# TSAL_Proto18_rev3.net
KiCad netlist of a schematic drawn in EAGLE
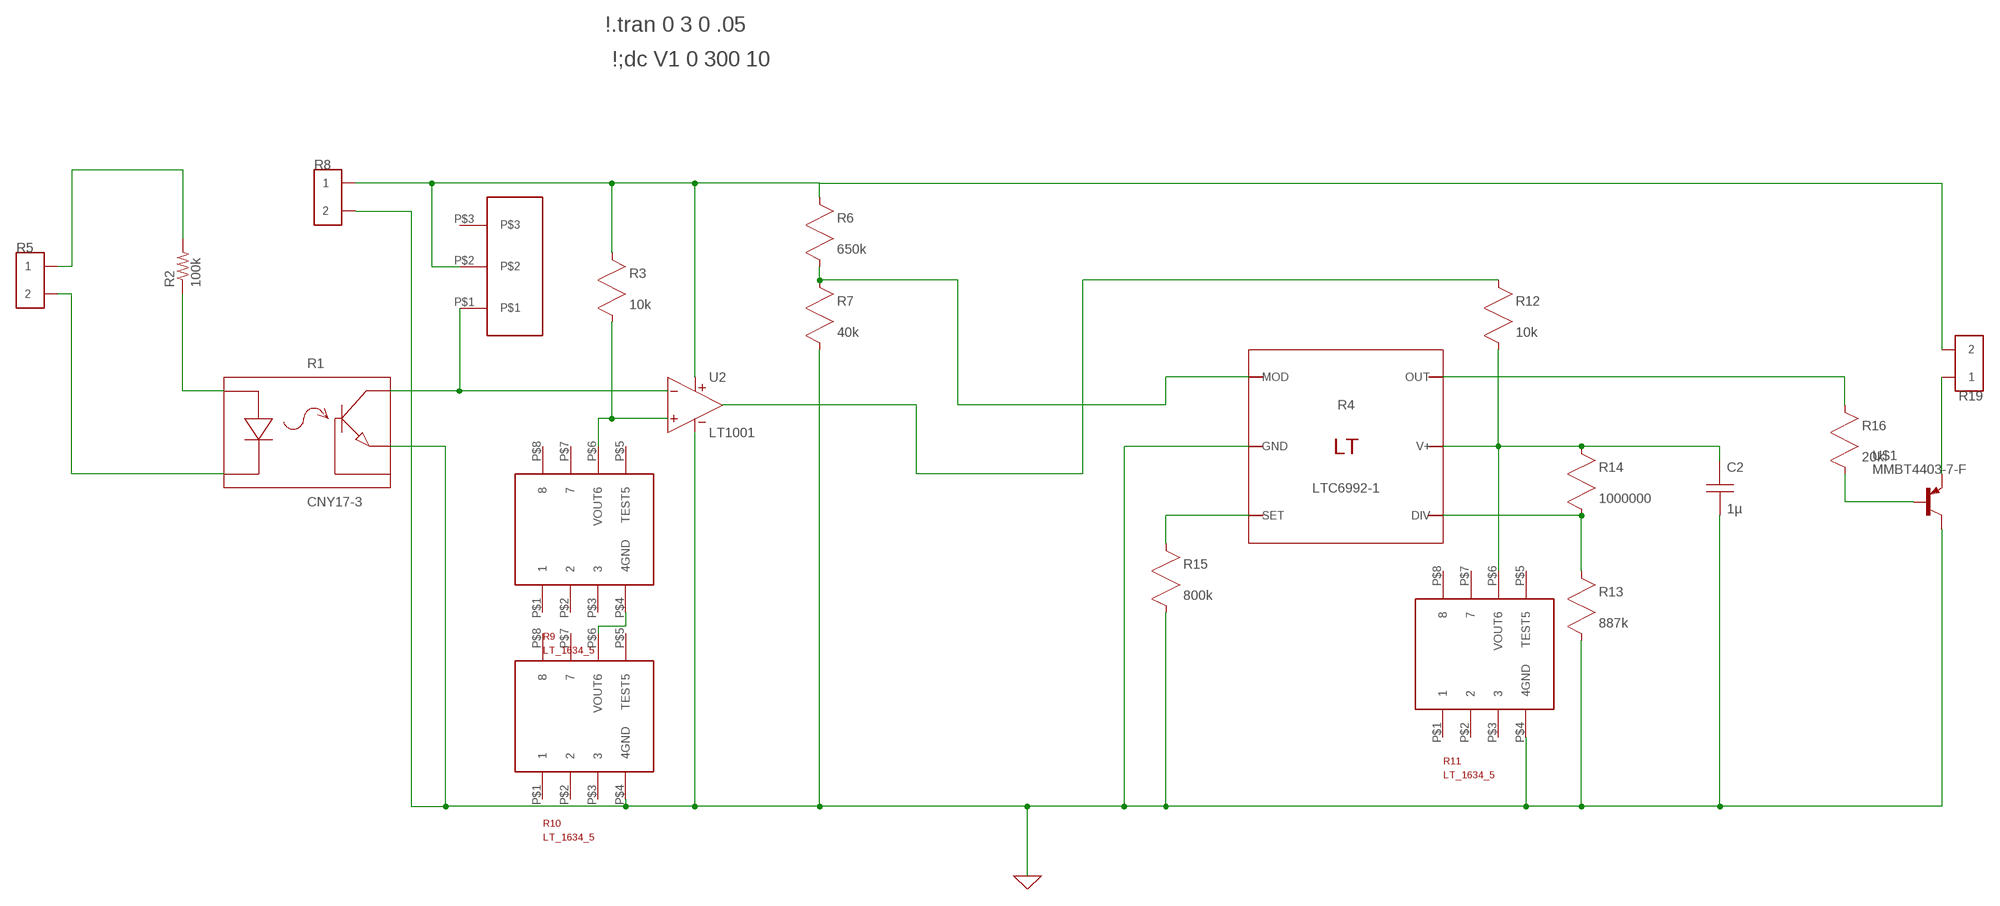
[diagram p0: schematic, sheet 1]

(export (version "E")
  (design (tool "Eeschema 10.0.6"))
  (components
    (comp (ref "C2")
      (value "1µ")
      (footprint "eagle-import:C0805")
      (libsource (lib "eagle-import") (part "CAP"))
    )
    (comp (ref "R1")
      (value "CNY17-3")
      (footprint "eagle-import:CNY17-3")
      (libsource (lib "eagle-import") (part "CNY17-3"))
    )
    (comp (ref "R2")
      (value "100k")
      (footprint "eagle-import:P0817_22")
      (libsource (lib "eagle-import") (part "R-US_0817/22"))
    )
    (comp (ref "R3")
      (value "10k")
      (footprint "eagle-import:R0805")
      (libsource (lib "eagle-import") (part "RES"))
    )
    (comp (ref "R4")
      (value "LTC6992-1")
      (footprint "eagle-import:LTC6992-1")
      (libsource (lib "eagle-import") (part "LTC6992-1"))
    )
    (comp (ref "R5")
      (value "CONN_2")
      (footprint "eagle-import:CONNECTOR_2")
      (libsource (lib "eagle-import") (part "CONN_2"))
    )
    (comp (ref "R6")
      (value "650k")
      (footprint "eagle-import:R0805")
      (libsource (lib "eagle-import") (part "RES"))
    )
    (comp (ref "R7")
      (value "40k")
      (footprint "eagle-import:R0805")
      (libsource (lib "eagle-import") (part "RES"))
    )
    (comp (ref "R8")
      (value "CONN_2")
      (footprint "eagle-import:CONNECTOR_2")
      (libsource (lib "eagle-import") (part "CONN_2"))
    )
    (comp (ref "R9")
      (value "LT_1634_5MS8")
      (footprint "eagle-import:LT_1634_5")
      (libsource (lib "eagle-import") (part "LT_1634_5MS8"))
    )
    (comp (ref "R10")
      (value "LT_1634_5MS8")
      (footprint "eagle-import:LT_1634_5")
      (libsource (lib "eagle-import") (part "LT_1634_5MS8"))
    )
    (comp (ref "R11")
      (value "LT_1634_5MS8")
      (footprint "eagle-import:LT_1634_5")
      (libsource (lib "eagle-import") (part "LT_1634_5MS8"))
    )
    (comp (ref "R12")
      (value "10k")
      (footprint "eagle-import:R0805")
      (libsource (lib "eagle-import") (part "RES"))
    )
    (comp (ref "R13")
      (value "887k")
      (footprint "eagle-import:R0805")
      (libsource (lib "eagle-import") (part "RES"))
    )
    (comp (ref "R14")
      (value "1000000")
      (footprint "eagle-import:R0805")
      (libsource (lib "eagle-import") (part "RES"))
    )
    (comp (ref "R15")
      (value "800k")
      (footprint "eagle-import:R0805")
      (libsource (lib "eagle-import") (part "RES"))
    )
    (comp (ref "R16")
      (value "20k")
      (footprint "eagle-import:R0805")
      (libsource (lib "eagle-import") (part "RES"))
    )
    (comp (ref "R19")
      (value "CONN_2")
      (footprint "eagle-import:CONNECTOR_2")
      (libsource (lib "eagle-import") (part "CONN_2"))
    )
    (comp (ref "U$1")
      (value "MMBT4403-7-F")
      (footprint "eagle-import:SOT-23-3")
      (libsource (lib "eagle-import") (part "MMBT4403-7-F"))
    )
    (comp (ref "U$2")
      (value "RK097111T")
      (footprint "eagle-import:RK097-POTENTIOMETER")
      (libsource (lib "eagle-import") (part "RK097111T"))
    )
    (comp (ref "U2")
      (value "LT1001")
      (footprint "eagle-import:S8")
      (libsource (lib "eagle-import") (part "LT1001"))
    )
  )
  (nets
    (net (code "1") (name "0") (class "Default")
      (node (ref "C2") (pin "2") (pinfunction "B_2") (pintype "passive"))
      (node (ref "R1") (pin "P$4") (pinfunction "E_P$4") (pintype "passive"))
      (node (ref "R10") (pin "P$4") (pinfunction "4GND_P$4") (pintype "bidirectional"))
      (node (ref "R11") (pin "P$4") (pinfunction "4GND_P$4") (pintype "bidirectional"))
      (node (ref "R13") (pin "2") (pinfunction "B_2") (pintype "passive"))
      (node (ref "R15") (pin "2") (pinfunction "B_2") (pintype "passive"))
      (node (ref "R4") (pin "P$2") (pinfunction "GND_P$2") (pintype "passive"))
      (node (ref "R7") (pin "2") (pinfunction "B_2") (pintype "passive"))
      (node (ref "R8") (pin "3") (pinfunction "2_3") (pintype "bidirectional"))
      (node (ref "R8") (pin "4") (pinfunction "2_4") (pintype "bidirectional"))
      (node (ref "U$1") (pin "P$1") (pinfunction "C_P$1") (pintype "passive"))
      (node (ref "U2") (pin "4") (pinfunction "V-_4") (pintype "passive"))
    )
    (net (code "2") (name "Net-(C2-A)") (class "Default")
      (node (ref "C2") (pin "1") (pinfunction "A_1") (pintype "passive"))
      (node (ref "R11") (pin "P$6") (pinfunction "VOUT6_P$6") (pintype "bidirectional"))
      (node (ref "R12") (pin "2") (pinfunction "B_2") (pintype "passive"))
      (node (ref "R14") (pin "1") (pinfunction "A_1") (pintype "passive"))
      (node (ref "R4") (pin "P$5") (pinfunction "V+_P$5") (pintype "passive"))
    )
    (net (code "3") (name "Net-(R1-A)") (class "Default")
      (node (ref "R1") (pin "P$1") (pinfunction "A_P$1") (pintype "passive"))
      (node (ref "R2") (pin "1") (pinfunction "1_1") (pintype "passive"))
    )
    (net (code "4") (name "Net-(R1-C)") (class "Default")
      (node (ref "R1") (pin "P$5") (pinfunction "C_P$5") (pintype "passive"))
      (node (ref "U$2") (pin "P$1") (pinfunction "P$1_P$1") (pintype "bidirectional"))
      (node (ref "U2") (pin "2") (pinfunction "IN-_2") (pintype "passive"))
    )
    (net (code "5") (name "Net-(R1-K)") (class "Default")
      (node (ref "R1") (pin "P$2") (pinfunction "K_P$2") (pintype "passive"))
      (node (ref "R5") (pin "3") (pinfunction "2_3") (pintype "bidirectional"))
      (node (ref "R5") (pin "4") (pinfunction "2_4") (pintype "bidirectional"))
    )
    (net (code "6") (name "Net-(R2-Pad2)") (class "Default")
      (node (ref "R2") (pin "2") (pinfunction "2_2") (pintype "passive"))
      (node (ref "R5") (pin "1") (pinfunction "1_1") (pintype "bidirectional"))
      (node (ref "R5") (pin "2") (pinfunction "1_2") (pintype "bidirectional"))
    )
    (net (code "7") (name "Net-(R3-A)") (class "Default")
      (node (ref "R19") (pin "3") (pinfunction "2_3") (pintype "bidirectional"))
      (node (ref "R19") (pin "4") (pinfunction "2_4") (pintype "bidirectional"))
      (node (ref "R3") (pin "1") (pinfunction "A_1") (pintype "passive"))
      (node (ref "R6") (pin "1") (pinfunction "A_1") (pintype "passive"))
      (node (ref "R8") (pin "1") (pinfunction "1_1") (pintype "bidirectional"))
      (node (ref "R8") (pin "2") (pinfunction "1_2") (pintype "bidirectional"))
      (node (ref "U$2") (pin "P$2") (pinfunction "P$2_P$2") (pintype "bidirectional"))
      (node (ref "U2") (pin "8") (pinfunction "V+_8") (pintype "passive"))
    )
    (net (code "8") (name "Net-(R3-B)") (class "Default")
      (node (ref "R3") (pin "2") (pinfunction "B_2") (pintype "passive"))
      (node (ref "R9") (pin "P$6") (pinfunction "VOUT6_P$6") (pintype "bidirectional"))
      (node (ref "U2") (pin "1") (pinfunction "IN+_1") (pintype "passive"))
    )
    (net (code "9") (name "Net-(R4-MOD)") (class "Default")
      (node (ref "R4") (pin "P$1") (pinfunction "MOD_P$1") (pintype "passive"))
      (node (ref "R6") (pin "2") (pinfunction "B_2") (pintype "passive"))
      (node (ref "R7") (pin "1") (pinfunction "A_1") (pintype "passive"))
    )
    (net (code "10") (name "Net-(R10-VOUT6)") (class "Default")
      (node (ref "R10") (pin "P$6") (pinfunction "VOUT6_P$6") (pintype "bidirectional"))
      (node (ref "R9") (pin "P$4") (pinfunction "4GND_P$4") (pintype "bidirectional"))
    )
    (net (code "11") (name "Net-(R12-A)") (class "Default")
      (node (ref "R12") (pin "1") (pinfunction "A_1") (pintype "passive"))
      (node (ref "U2") (pin "3") (pinfunction "OUT_3") (pintype "passive"))
    )
    (net (code "12") (name "Net-(R13-A)") (class "Default")
      (node (ref "R13") (pin "1") (pinfunction "A_1") (pintype "passive"))
      (node (ref "R14") (pin "2") (pinfunction "B_2") (pintype "passive"))
      (node (ref "R4") (pin "P$4") (pinfunction "DIV_P$4") (pintype "passive"))
    )
    (net (code "13") (name "Net-(R15-A)") (class "Default")
      (node (ref "R15") (pin "1") (pinfunction "A_1") (pintype "passive"))
      (node (ref "R4") (pin "P$3") (pinfunction "SET_P$3") (pintype "passive"))
    )
    (net (code "14") (name "Net-(R16-A)") (class "Default")
      (node (ref "R16") (pin "1") (pinfunction "A_1") (pintype "passive"))
      (node (ref "R4") (pin "P$6") (pinfunction "OUT_P$6") (pintype "passive"))
    )
    (net (code "15") (name "Net-(R16-B)") (class "Default")
      (node (ref "R16") (pin "2") (pinfunction "B_2") (pintype "passive"))
      (node (ref "U$1") (pin "P$2") (pinfunction "B_P$2") (pintype "passive"))
    )
    (net (code "16") (name "Net-(U$1-E)") (class "Default")
      (node (ref "R19") (pin "1") (pinfunction "1_1") (pintype "bidirectional"))
      (node (ref "R19") (pin "2") (pinfunction "1_2") (pintype "bidirectional"))
      (node (ref "U$1") (pin "P$3") (pinfunction "E_P$3") (pintype "passive"))
    )
    (net (code "17") (name "unconnected-(R1-B-PadP$6)") (class "Default")
      (node (ref "R1") (pin "P$6") (pinfunction "B_P$6") (pintype "passive"))
    )
    (net (code "18") (name "unconnected-(R9-1-PadP$1)") (class "Default")
      (node (ref "R9") (pin "P$1") (pinfunction "1_P$1") (pintype "bidirectional"))
    )
    (net (code "19") (name "unconnected-(R9-2-PadP$2)") (class "Default")
      (node (ref "R9") (pin "P$2") (pinfunction "2_P$2") (pintype "bidirectional"))
    )
    (net (code "20") (name "unconnected-(R9-3-PadP$3)") (class "Default")
      (node (ref "R9") (pin "P$3") (pinfunction "3_P$3") (pintype "bidirectional"))
    )
    (net (code "21") (name "unconnected-(R9-7-PadP$7)") (class "Default")
      (node (ref "R9") (pin "P$7") (pinfunction "7_P$7") (pintype "bidirectional"))
    )
    (net (code "22") (name "unconnected-(R9-8-PadP$8)") (class "Default")
      (node (ref "R9") (pin "P$8") (pinfunction "8_P$8") (pintype "bidirectional"))
    )
    (net (code "23") (name "unconnected-(R9-TEST5-PadP$5)") (class "Default")
      (node (ref "R9") (pin "P$5") (pinfunction "TEST5_P$5") (pintype "bidirectional"))
    )
    (net (code "24") (name "unconnected-(R10-1-PadP$1)") (class "Default")
      (node (ref "R10") (pin "P$1") (pinfunction "1_P$1") (pintype "bidirectional"))
    )
    (net (code "25") (name "unconnected-(R10-2-PadP$2)") (class "Default")
      (node (ref "R10") (pin "P$2") (pinfunction "2_P$2") (pintype "bidirectional"))
    )
    (net (code "26") (name "unconnected-(R10-3-PadP$3)") (class "Default")
      (node (ref "R10") (pin "P$3") (pinfunction "3_P$3") (pintype "bidirectional"))
    )
    (net (code "27") (name "unconnected-(R10-7-PadP$7)") (class "Default")
      (node (ref "R10") (pin "P$7") (pinfunction "7_P$7") (pintype "bidirectional"))
    )
    (net (code "28") (name "unconnected-(R10-8-PadP$8)") (class "Default")
      (node (ref "R10") (pin "P$8") (pinfunction "8_P$8") (pintype "bidirectional"))
    )
    (net (code "29") (name "unconnected-(R10-TEST5-PadP$5)") (class "Default")
      (node (ref "R10") (pin "P$5") (pinfunction "TEST5_P$5") (pintype "bidirectional"))
    )
    (net (code "30") (name "unconnected-(R11-1-PadP$1)") (class "Default")
      (node (ref "R11") (pin "P$1") (pinfunction "1_P$1") (pintype "bidirectional"))
    )
    (net (code "31") (name "unconnected-(R11-2-PadP$2)") (class "Default")
      (node (ref "R11") (pin "P$2") (pinfunction "2_P$2") (pintype "bidirectional"))
    )
    (net (code "32") (name "unconnected-(R11-3-PadP$3)") (class "Default")
      (node (ref "R11") (pin "P$3") (pinfunction "3_P$3") (pintype "bidirectional"))
    )
    (net (code "33") (name "unconnected-(R11-7-PadP$7)") (class "Default")
      (node (ref "R11") (pin "P$7") (pinfunction "7_P$7") (pintype "bidirectional"))
    )
    (net (code "34") (name "unconnected-(R11-8-PadP$8)") (class "Default")
      (node (ref "R11") (pin "P$8") (pinfunction "8_P$8") (pintype "bidirectional"))
    )
    (net (code "35") (name "unconnected-(R11-TEST5-PadP$5)") (class "Default")
      (node (ref "R11") (pin "P$5") (pinfunction "TEST5_P$5") (pintype "bidirectional"))
    )
    (net (code "36") (name "unconnected-(U$2-PadP$3)") (class "Default")
      (node (ref "U$2") (pin "P$3") (pinfunction "P$3_P$3") (pintype "bidirectional"))
    )
  )
)
